# Sensor_ESP32_1_1.net
KiCad netlist of a schematic drawn in EAGLE
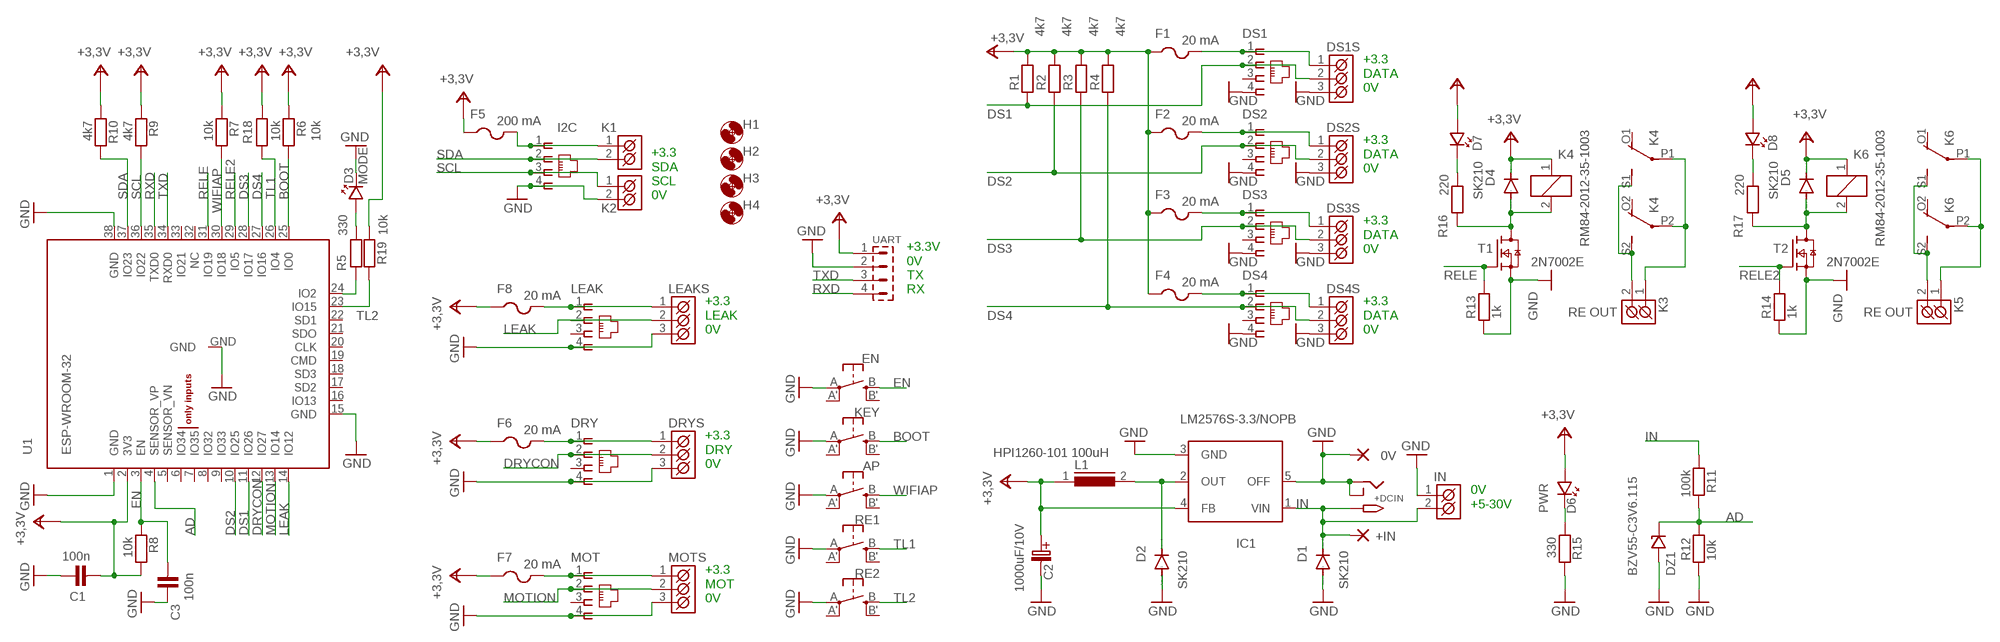
[diagram p0: schematic, sheet 1]

(export (version "E")
  (design (tool "Eeschema 10.0.6"))
  (components
    (comp (ref "+DCIN")
      (value "2.1MMJACKTHM")
      (footprint "eagle-import:PJ-102A")
      (libsource (lib "eagle-import") (part "2.1MMJACKTHM"))
    )
    (comp (ref "+IN")
      (value "SMD2")
      (footprint "eagle-import:SMD1,27-2,54")
      (libsource (lib "eagle-import") (part "SMD2"))
    )
    (comp (ref "0V")
      (value "SMD2")
      (footprint "eagle-import:SMD1,27-2,54")
      (libsource (lib "eagle-import") (part "SMD2"))
    )
    (comp (ref "AP")
      (value "SPST_TACT-EVQQ2")
      (footprint "eagle-import:EVQ-Q2")
      (libsource (lib "eagle-import") (part "SPST_TACT-EVQQ2"))
    )
    (comp (ref "C1")
      (value "100n")
      (footprint "eagle-import:1206")
      (libsource (lib "eagle-import") (part "C-KER_1206"))
    )
    (comp (ref "C2")
      (value "1000uF/10V")
      (footprint "eagle-import:C-EL_5")
      (libsource (lib "eagle-import") (part "C-EL_5"))
    )
    (comp (ref "C3")
      (value "100n")
      (footprint "eagle-import:1206")
      (libsource (lib "eagle-import") (part "C-KER_1206"))
    )
    (comp (ref "D1")
      (value "SK210")
      (footprint "eagle-import:SMB")
      (libsource (lib "eagle-import") (part "DIODE-SMB"))
    )
    (comp (ref "D2")
      (value "SK210")
      (footprint "eagle-import:SMB")
      (libsource (lib "eagle-import") (part "DIODE-SMB"))
    )
    (comp (ref "D3")
      (value "MODE")
      (footprint "eagle-import:P1206")
      (libsource (lib "eagle-import") (part "LED_1206"))
    )
    (comp (ref "D4")
      (value "SK210")
      (footprint "eagle-import:SMB")
      (libsource (lib "eagle-import") (part "DIODE-SMB"))
    )
    (comp (ref "D5")
      (value "SK210")
      (footprint "eagle-import:SMB")
      (libsource (lib "eagle-import") (part "DIODE-SMB"))
    )
    (comp (ref "D6")
      (value "PWR")
      (footprint "eagle-import:P1206")
      (libsource (lib "eagle-import") (part "LED_1206"))
    )
    (comp (ref "D7")
      (value "LED_1206")
      (footprint "eagle-import:P1206")
      (libsource (lib "eagle-import") (part "LED_1206"))
    )
    (comp (ref "D8")
      (value "LED_1206")
      (footprint "eagle-import:P1206")
      (libsource (lib "eagle-import") (part "LED_1206"))
    )
    (comp (ref "DRY")
      (value "WEBP_6_1")
      (footprint "eagle-import:WEBP_6_1")
      (libsource (lib "eagle-import") (part "WEBP_6_1"))
    )
    (comp (ref "DRYS")
      (value "ARK550/3")
      (footprint "eagle-import:ARK550_3")
      (libsource (lib "eagle-import") (part "ARK550/3"))
    )
    (comp (ref "DS1")
      (value "WEBP_6_1")
      (footprint "eagle-import:WEBP_6_1")
      (libsource (lib "eagle-import") (part "WEBP_6_1"))
    )
    (comp (ref "DS1S")
      (value "ARK550/3")
      (footprint "eagle-import:ARK550_3")
      (libsource (lib "eagle-import") (part "ARK550/3"))
    )
    (comp (ref "DS2")
      (value "WEBP_6_1")
      (footprint "eagle-import:WEBP_6_1")
      (libsource (lib "eagle-import") (part "WEBP_6_1"))
    )
    (comp (ref "DS2S")
      (value "ARK550/3")
      (footprint "eagle-import:ARK550_3")
      (libsource (lib "eagle-import") (part "ARK550/3"))
    )
    (comp (ref "DS3")
      (value "WEBP_6_1")
      (footprint "eagle-import:WEBP_6_1")
      (libsource (lib "eagle-import") (part "WEBP_6_1"))
    )
    (comp (ref "DS3S")
      (value "ARK550/3")
      (footprint "eagle-import:ARK550_3")
      (libsource (lib "eagle-import") (part "ARK550/3"))
    )
    (comp (ref "DS4")
      (value "WEBP_6_1")
      (footprint "eagle-import:WEBP_6_1")
      (libsource (lib "eagle-import") (part "WEBP_6_1"))
    )
    (comp (ref "DS4S")
      (value "ARK550/3")
      (footprint "eagle-import:ARK550_3")
      (libsource (lib "eagle-import") (part "ARK550/3"))
    )
    (comp (ref "DZ1")
      (value "BZV55-C3V6.115")
      (footprint "eagle-import:SOD-80")
      (libsource (lib "eagle-import") (part "D-?-ZENERBZV55C_SMD_0,5W"))
    )
    (comp (ref "EN")
      (value "SPST_TACT-EVQQ2")
      (footprint "eagle-import:EVQ-Q2")
      (libsource (lib "eagle-import") (part "SPST_TACT-EVQQ2"))
    )
    (comp (ref "F1")
      (value "20 mA")
      (footprint "eagle-import:R1206")
      (libsource (lib "eagle-import") (part "PTCFUSE-1206"))
    )
    (comp (ref "F2")
      (value "20 mA")
      (footprint "eagle-import:R1206")
      (libsource (lib "eagle-import") (part "PTCFUSE-1206"))
    )
    (comp (ref "F3")
      (value "20 mA")
      (footprint "eagle-import:R1206")
      (libsource (lib "eagle-import") (part "PTCFUSE-1206"))
    )
    (comp (ref "F4")
      (value "20 mA")
      (footprint "eagle-import:R1206")
      (libsource (lib "eagle-import") (part "PTCFUSE-1206"))
    )
    (comp (ref "F5")
      (value "200 mA")
      (footprint "eagle-import:R1206")
      (libsource (lib "eagle-import") (part "PTCFUSE-1206"))
    )
    (comp (ref "F6")
      (value "20 mA")
      (footprint "eagle-import:R1206")
      (libsource (lib "eagle-import") (part "PTCFUSE-1206"))
    )
    (comp (ref "F7")
      (value "20 mA")
      (footprint "eagle-import:R1206")
      (libsource (lib "eagle-import") (part "PTCFUSE-1206"))
    )
    (comp (ref "F8")
      (value "20 mA")
      (footprint "eagle-import:R1206")
      (libsource (lib "eagle-import") (part "PTCFUSE-1206"))
    )
    (comp (ref "H1")
      (value "MOUNT-HOLE3.0")
      (footprint "eagle-import:3,0")
      (libsource (lib "eagle-import") (part "MOUNT-HOLE3.0"))
    )
    (comp (ref "H2")
      (value "MOUNT-HOLE3.0")
      (footprint "eagle-import:3,0")
      (libsource (lib "eagle-import") (part "MOUNT-HOLE3.0"))
    )
    (comp (ref "H3")
      (value "MOUNT-HOLE3.0")
      (footprint "eagle-import:3,0")
      (libsource (lib "eagle-import") (part "MOUNT-HOLE3.0"))
    )
    (comp (ref "H4")
      (value "MOUNT-HOLE3.0")
      (footprint "eagle-import:3,0")
      (libsource (lib "eagle-import") (part "MOUNT-HOLE3.0"))
    )
    (comp (ref "I2C")
      (value "WEBP_6_1")
      (footprint "eagle-import:WEBP_6_1")
      (libsource (lib "eagle-import") (part "WEBP_6_1"))
    )
    (comp (ref "IC1")
      (value "LM2576S-3.3/NOPB")
      (footprint "eagle-import:TO263-5")
      (libsource (lib "eagle-import") (part "LM2576S"))
    )
    (comp (ref "IN")
      (value "ARK550/2")
      (footprint "eagle-import:ARK550_2")
      (libsource (lib "eagle-import") (part "ARK550/2"))
    )
    (comp (ref "K1")
      (value "ARK550/2")
      (footprint "eagle-import:ARK550_2")
      (libsource (lib "eagle-import") (part "ARK550/2"))
    )
    (comp (ref "K2")
      (value "ARK550/2")
      (footprint "eagle-import:ARK550_2")
      (libsource (lib "eagle-import") (part "ARK550/2"))
    )
    (comp (ref "K3")
      (value "RE OUT")
      (footprint "eagle-import:ARK500_2")
      (libsource (lib "eagle-import") (part "ARK500/2"))
    )
    (comp (ref "K4")
      (value "RM84-2012-35-1003")
      (footprint "eagle-import:G2R2")
      (fields (field (name "MF") "OMRON COMPONENTS USA") (field (name "MPN") "G2R-2-DC6"))
      (libsource (lib "eagle-import") (part "G2R2"))
    )
    (comp (ref "K5")
      (value "RE OUT")
      (footprint "eagle-import:ARK500_2")
      (libsource (lib "eagle-import") (part "ARK500/2"))
    )
    (comp (ref "K6")
      (value "RM84-2012-35-1003")
      (footprint "eagle-import:G2R2")
      (fields (field (name "MF") "OMRON COMPONENTS USA") (field (name "MPN") "G2R-2-DC6"))
      (libsource (lib "eagle-import") (part "G2R2"))
    )
    (comp (ref "KEY")
      (value "SPST_TACT-EVQQ2")
      (footprint "eagle-import:EVQ-Q2")
      (libsource (lib "eagle-import") (part "SPST_TACT-EVQQ2"))
    )
    (comp (ref "L1")
      (value "HPI1260-101 100uH")
      (footprint "eagle-import:DR125")
      (libsource (lib "eagle-import") (part "DR125"))
    )
    (comp (ref "LEAK")
      (value "WEBP_6_1")
      (footprint "eagle-import:WEBP_6_1")
      (libsource (lib "eagle-import") (part "WEBP_6_1"))
    )
    (comp (ref "LEAKS")
      (value "ARK550/3")
      (footprint "eagle-import:ARK550_3")
      (libsource (lib "eagle-import") (part "ARK550/3"))
    )
    (comp (ref "MOT")
      (value "WEBP_6_1")
      (footprint "eagle-import:WEBP_6_1")
      (libsource (lib "eagle-import") (part "WEBP_6_1"))
    )
    (comp (ref "MOTS")
      (value "ARK550/3")
      (footprint "eagle-import:ARK550_3")
      (libsource (lib "eagle-import") (part "ARK550/3"))
    )
    (comp (ref "R1")
      (value "4k7")
      (footprint "eagle-import:1206")
      (libsource (lib "eagle-import") (part "R_1206"))
    )
    (comp (ref "R2")
      (value "4k7")
      (footprint "eagle-import:1206")
      (libsource (lib "eagle-import") (part "R_1206"))
    )
    (comp (ref "R3")
      (value "4k7")
      (footprint "eagle-import:1206")
      (libsource (lib "eagle-import") (part "R_1206"))
    )
    (comp (ref "R4")
      (value "4k7")
      (footprint "eagle-import:1206")
      (libsource (lib "eagle-import") (part "R_1206"))
    )
    (comp (ref "R5")
      (value "330")
      (footprint "eagle-import:1206")
      (libsource (lib "eagle-import") (part "R_1206"))
    )
    (comp (ref "R6")
      (value "10k")
      (footprint "eagle-import:1206")
      (libsource (lib "eagle-import") (part "R_1206"))
    )
    (comp (ref "R7")
      (value "10k")
      (footprint "eagle-import:1206")
      (libsource (lib "eagle-import") (part "R_1206"))
    )
    (comp (ref "R8")
      (value "10k")
      (footprint "eagle-import:1206")
      (libsource (lib "eagle-import") (part "R_1206"))
    )
    (comp (ref "R9")
      (value "4k7")
      (footprint "eagle-import:1206")
      (libsource (lib "eagle-import") (part "R_1206"))
    )
    (comp (ref "R10")
      (value "4k7")
      (footprint "eagle-import:1206")
      (libsource (lib "eagle-import") (part "R_1206"))
    )
    (comp (ref "R11")
      (value "100k")
      (footprint "eagle-import:1206")
      (libsource (lib "eagle-import") (part "R_1206"))
    )
    (comp (ref "R12")
      (value "10k")
      (footprint "eagle-import:1206")
      (libsource (lib "eagle-import") (part "R_1206"))
    )
    (comp (ref "R13")
      (value "1k")
      (footprint "eagle-import:1206")
      (libsource (lib "eagle-import") (part "R_1206"))
    )
    (comp (ref "R14")
      (value "1k")
      (footprint "eagle-import:1206")
      (libsource (lib "eagle-import") (part "R_1206"))
    )
    (comp (ref "R15")
      (value "330")
      (footprint "eagle-import:1206")
      (libsource (lib "eagle-import") (part "R_1206"))
    )
    (comp (ref "R16")
      (value "220")
      (footprint "eagle-import:1206")
      (libsource (lib "eagle-import") (part "R_1206"))
    )
    (comp (ref "R17")
      (value "220")
      (footprint "eagle-import:1206")
      (libsource (lib "eagle-import") (part "R_1206"))
    )
    (comp (ref "R18")
      (value "10k")
      (footprint "eagle-import:1206")
      (libsource (lib "eagle-import") (part "R_1206"))
    )
    (comp (ref "R19")
      (value "10k")
      (footprint "eagle-import:1206")
      (libsource (lib "eagle-import") (part "R_1206"))
    )
    (comp (ref "RE1")
      (value "SPST_TACT-EVQQ2")
      (footprint "eagle-import:EVQ-Q2")
      (libsource (lib "eagle-import") (part "SPST_TACT-EVQQ2"))
    )
    (comp (ref "RE2")
      (value "SPST_TACT-EVQQ2")
      (footprint "eagle-import:EVQ-Q2")
      (libsource (lib "eagle-import") (part "SPST_TACT-EVQQ2"))
    )
    (comp (ref "T1")
      (value "2N7002E")
      (footprint "eagle-import:SOT23")
      (libsource (lib "eagle-import") (part "2N7002E"))
    )
    (comp (ref "T2")
      (value "2N7002E")
      (footprint "eagle-import:SOT23")
      (libsource (lib "eagle-import") (part "2N7002E"))
    )
    (comp (ref "U1")
      (value "ESP-WROOM-32")
      (footprint "eagle-import:ESP-WROOM-32")
      (libsource (lib "eagle-import") (part "ESP-WROOM-32"))
    )
    (comp (ref "UART")
      (value "S1G4_JUMP")
      (footprint "eagle-import:S1G4_JUM")
      (libsource (lib "eagle-import") (part "S1G4_JUMP"))
    )
  )
  (nets
    (net (code "1") (name "+3,3V") (class "Default")
      (node (ref "C1") (pin "2") (pinfunction "2_2") (pintype "passive"))
      (node (ref "C2") (pin "C+") (pinfunction "C_EL+_C+") (pintype "passive"))
      (node (ref "D4") (pin "C") (pinfunction "C_C") (pintype "passive"))
      (node (ref "D5") (pin "C") (pinfunction "C_C") (pintype "passive"))
      (node (ref "D6") (pin "A") (pinfunction "A_A") (pintype "passive"))
      (node (ref "D7") (pin "A") (pinfunction "A_A") (pintype "passive"))
      (node (ref "D8") (pin "A") (pinfunction "A_A") (pintype "passive"))
      (node (ref "F1") (pin "1") (pinfunction "1_1") (pintype "passive"))
      (node (ref "F2") (pin "1") (pinfunction "1_1") (pintype "passive"))
      (node (ref "F3") (pin "1") (pinfunction "1_1") (pintype "passive"))
      (node (ref "F4") (pin "1") (pinfunction "1_1") (pintype "passive"))
      (node (ref "F5") (pin "1") (pinfunction "1_1") (pintype "passive"))
      (node (ref "F6") (pin "1") (pinfunction "1_1") (pintype "passive"))
      (node (ref "F7") (pin "1") (pinfunction "1_1") (pintype "passive"))
      (node (ref "F8") (pin "1") (pinfunction "1_1") (pintype "passive"))
      (node (ref "IC1") (pin "4") (pinfunction "FB_4") (pintype "input"))
      (node (ref "K4") (pin "1") (pinfunction "1_1") (pintype "passive"))
      (node (ref "K6") (pin "1") (pinfunction "1_1") (pintype "passive"))
      (node (ref "L1") (pin "1") (pinfunction "1_1") (pintype "passive"))
      (node (ref "R1") (pin "2") (pinfunction "2_2") (pintype "passive"))
      (node (ref "R10") (pin "1") (pinfunction "1_1") (pintype "passive"))
      (node (ref "R18") (pin "1") (pinfunction "1_1") (pintype "passive"))
      (node (ref "R19") (pin "1") (pinfunction "1_1") (pintype "passive"))
      (node (ref "R2") (pin "2") (pinfunction "2_2") (pintype "passive"))
      (node (ref "R3") (pin "2") (pinfunction "2_2") (pintype "passive"))
      (node (ref "R4") (pin "2") (pinfunction "2_2") (pintype "passive"))
      (node (ref "R6") (pin "1") (pinfunction "1_1") (pintype "passive"))
      (node (ref "R7") (pin "1") (pinfunction "1_1") (pintype "passive"))
      (node (ref "R8") (pin "2") (pinfunction "2_2") (pintype "passive"))
      (node (ref "R9") (pin "1") (pinfunction "1_1") (pintype "passive"))
      (node (ref "U1") (pin "2") (pinfunction "3V3_2") (pintype "bidirectional"))
      (node (ref "UART") (pin "1") (pinfunction "1_1") (pintype "passive"))
    )
    (net (code "2") (name "/AD") (class "Default")
      (node (ref "DZ1") (pin "K") (pinfunction "K_K") (pintype "passive"))
      (node (ref "R11") (pin "2") (pinfunction "2_2") (pintype "passive"))
      (node (ref "R12") (pin "2") (pinfunction "2_2") (pintype "passive"))
      (node (ref "U1") (pin "4") (pinfunction "SENSOR_VP_4") (pintype "input"))
    )
    (net (code "3") (name "/BOOT") (class "Default")
      (node (ref "KEY") (pin "B") (pinfunction "S_B") (pintype "passive"))
      (node (ref "R6") (pin "2") (pinfunction "2_2") (pintype "passive"))
      (node (ref "U1") (pin "25") (pinfunction "IO0_25") (pintype "bidirectional"))
    )
    (net (code "4") (name "/DRYCON") (class "Default")
      (node (ref "DRY") (pin "2") (pinfunction "2_2") (pintype "passive"))
      (node (ref "DRYS") (pin "2") (pinfunction "K2_2") (pintype "passive"))
      (node (ref "U1") (pin "12") (pinfunction "IO27_12") (pintype "bidirectional"))
    )
    (net (code "5") (name "/DS1") (class "Default")
      (node (ref "DS1") (pin "2") (pinfunction "2_2") (pintype "passive"))
      (node (ref "DS1S") (pin "2") (pinfunction "K2_2") (pintype "passive"))
      (node (ref "R1") (pin "1") (pinfunction "1_1") (pintype "passive"))
      (node (ref "U1") (pin "11") (pinfunction "IO26_11") (pintype "bidirectional"))
    )
    (net (code "6") (name "/DS2") (class "Default")
      (node (ref "DS2") (pin "2") (pinfunction "2_2") (pintype "passive"))
      (node (ref "DS2S") (pin "2") (pinfunction "K2_2") (pintype "passive"))
      (node (ref "R2") (pin "1") (pinfunction "1_1") (pintype "passive"))
      (node (ref "U1") (pin "10") (pinfunction "IO25_10") (pintype "bidirectional"))
    )
    (net (code "7") (name "/DS3") (class "Default")
      (node (ref "DS3") (pin "2") (pinfunction "2_2") (pintype "passive"))
      (node (ref "DS3S") (pin "2") (pinfunction "K2_2") (pintype "passive"))
      (node (ref "R3") (pin "1") (pinfunction "1_1") (pintype "passive"))
      (node (ref "U1") (pin "28") (pinfunction "IO17_28") (pintype "bidirectional"))
    )
    (net (code "8") (name "/DS4") (class "Default")
      (node (ref "DS4") (pin "2") (pinfunction "2_2") (pintype "passive"))
      (node (ref "DS4S") (pin "2") (pinfunction "K2_2") (pintype "passive"))
      (node (ref "R4") (pin "1") (pinfunction "1_1") (pintype "passive"))
      (node (ref "U1") (pin "27") (pinfunction "IO16_27") (pintype "bidirectional"))
    )
    (net (code "9") (name "/EN") (class "Default")
      (node (ref "C3") (pin "2") (pinfunction "2_2") (pintype "passive"))
      (node (ref "EN") (pin "B") (pinfunction "S_B") (pintype "passive"))
      (node (ref "R8") (pin "1") (pinfunction "1_1") (pintype "passive"))
      (node (ref "U1") (pin "3") (pinfunction "EN_3") (pintype "bidirectional"))
    )
    (net (code "10") (name "/IN") (class "Default")
      (node (ref "+DCIN") (pin "TIP") (pinfunction "TIP_TIP") (pintype "bidirectional"))
      (node (ref "+IN") (pin "1") (pinfunction "P_1") (pintype "passive"))
      (node (ref "D1") (pin "C") (pinfunction "C_C") (pintype "passive"))
      (node (ref "IC1") (pin "1") (pinfunction "VIN_1") (pintype "power_in"))
      (node (ref "IN") (pin "2") (pinfunction "K2_2") (pintype "passive"))
      (node (ref "R11") (pin "1") (pinfunction "1_1") (pintype "passive"))
    )
    (net (code "11") (name "/LEAK") (class "Default")
      (node (ref "LEAK") (pin "2") (pinfunction "2_2") (pintype "passive"))
      (node (ref "LEAKS") (pin "2") (pinfunction "K2_2") (pintype "passive"))
      (node (ref "U1") (pin "14") (pinfunction "IO12_14") (pintype "bidirectional"))
    )
    (net (code "12") (name "/MOTION") (class "Default")
      (node (ref "MOT") (pin "2") (pinfunction "2_2") (pintype "passive"))
      (node (ref "MOTS") (pin "2") (pinfunction "K2_2") (pintype "passive"))
      (node (ref "U1") (pin "13") (pinfunction "IO14_13") (pintype "bidirectional"))
    )
    (net (code "13") (name "/RELE") (class "Default")
      (node (ref "R13") (pin "2") (pinfunction "2_2") (pintype "passive"))
      (node (ref "T1") (pin "1") (pinfunction "G_1") (pintype "passive"))
      (node (ref "U1") (pin "31") (pinfunction "IO19_31") (pintype "bidirectional"))
    )
    (net (code "14") (name "/RELE2") (class "Default")
      (node (ref "R14") (pin "2") (pinfunction "2_2") (pintype "passive"))
      (node (ref "T2") (pin "1") (pinfunction "G_1") (pintype "passive"))
      (node (ref "U1") (pin "29") (pinfunction "IO5_29") (pintype "bidirectional"))
    )
    (net (code "15") (name "/RXD") (class "Default")
      (node (ref "U1") (pin "35") (pinfunction "TXD0_35") (pintype "bidirectional"))
      (node (ref "UART") (pin "4") (pinfunction "4_4") (pintype "passive"))
    )
    (net (code "16") (name "/SCL") (class "Default")
      (node (ref "I2C") (pin "3") (pinfunction "3_3") (pintype "passive"))
      (node (ref "K2") (pin "1") (pinfunction "K1_1") (pintype "passive"))
      (node (ref "R9") (pin "2") (pinfunction "2_2") (pintype "passive"))
      (node (ref "U1") (pin "36") (pinfunction "IO22_36") (pintype "bidirectional"))
    )
    (net (code "17") (name "/SDA") (class "Default")
      (node (ref "I2C") (pin "2") (pinfunction "2_2") (pintype "passive"))
      (node (ref "K1") (pin "2") (pinfunction "K2_2") (pintype "passive"))
      (node (ref "R10") (pin "2") (pinfunction "2_2") (pintype "passive"))
      (node (ref "U1") (pin "37") (pinfunction "IO23_37") (pintype "bidirectional"))
    )
    (net (code "18") (name "/TL1") (class "Default")
      (node (ref "R18") (pin "2") (pinfunction "2_2") (pintype "passive"))
      (node (ref "RE1") (pin "B") (pinfunction "S_B") (pintype "passive"))
      (node (ref "U1") (pin "26") (pinfunction "IO4_26") (pintype "bidirectional"))
    )
    (net (code "19") (name "/TL2") (class "Default")
      (node (ref "R19") (pin "2") (pinfunction "2_2") (pintype "passive"))
      (node (ref "RE2") (pin "B") (pinfunction "S_B") (pintype "passive"))
      (node (ref "U1") (pin "23") (pinfunction "IO15_23") (pintype "bidirectional"))
    )
    (net (code "20") (name "/TXD") (class "Default")
      (node (ref "U1") (pin "34") (pinfunction "RXD0_34") (pintype "bidirectional"))
      (node (ref "UART") (pin "3") (pinfunction "3_3") (pintype "passive"))
    )
    (net (code "21") (name "/WIFIAP") (class "Default")
      (node (ref "AP") (pin "B") (pinfunction "S_B") (pintype "passive"))
      (node (ref "R7") (pin "2") (pinfunction "2_2") (pintype "passive"))
      (node (ref "U1") (pin "30") (pinfunction "IO18_30") (pintype "bidirectional"))
    )
    (net (code "22") (name "GND") (class "Default")
      (node (ref "+DCIN") (pin "RING") (pinfunction "RING_RING") (pintype "bidirectional"))
      (node (ref "+DCIN") (pin "RING_SW") (pinfunction "RING_SW_RING_SW") (pintype "bidirectional"))
      (node (ref "0V") (pin "1") (pinfunction "P_1") (pintype "passive"))
      (node (ref "AP") (pin "A") (pinfunction "P_A") (pintype "passive"))
      (node (ref "C1") (pin "1") (pinfunction "1_1") (pintype "passive"))
      (node (ref "C2") (pin "C-") (pinfunction "C_EL-_C-") (pintype "passive"))
      (node (ref "C3") (pin "1") (pinfunction "1_1") (pintype "passive"))
      (node (ref "D1") (pin "A") (pinfunction "A_A") (pintype "passive"))
      (node (ref "D2") (pin "A") (pinfunction "A_A") (pintype "passive"))
      (node (ref "D3") (pin "K") (pinfunction "K_K") (pintype "passive"))
      (node (ref "DRY") (pin "4") (pinfunction "4_4") (pintype "passive"))
      (node (ref "DRYS") (pin "3") (pinfunction "K3_3") (pintype "passive"))
      (node (ref "DS1") (pin "4") (pinfunction "4_4") (pintype "passive"))
      (node (ref "DS1S") (pin "3") (pinfunction "K3_3") (pintype "passive"))
      (node (ref "DS2") (pin "4") (pinfunction "4_4") (pintype "passive"))
      (node (ref "DS2S") (pin "3") (pinfunction "K3_3") (pintype "passive"))
      (node (ref "DS3") (pin "4") (pinfunction "4_4") (pintype "passive"))
      (node (ref "DS3S") (pin "3") (pinfunction "K3_3") (pintype "passive"))
      (node (ref "DS4") (pin "4") (pinfunction "4_4") (pintype "passive"))
      (node (ref "DS4S") (pin "3") (pinfunction "K3_3") (pintype "passive"))
      (node (ref "DZ1") (pin "A") (pinfunction "A_A") (pintype "passive"))
      (node (ref "EN") (pin "A") (pinfunction "P_A") (pintype "passive"))
      (node (ref "I2C") (pin "4") (pinfunction "4_4") (pintype "passive"))
      (node (ref "IC1") (pin "3") (pinfunction "GND_3") (pintype "power_in"))
      (node (ref "IC1") (pin "5") (pinfunction "OFF_5") (pintype "input"))
      (node (ref "IN") (pin "1") (pinfunction "K1_1") (pintype "passive"))
      (node (ref "K2") (pin "2") (pinfunction "K2_2") (pintype "passive"))
      (node (ref "KEY") (pin "A") (pinfunction "P_A") (pintype "passive"))
      (node (ref "LEAK") (pin "4") (pinfunction "4_4") (pintype "passive"))
      (node (ref "LEAKS") (pin "3") (pinfunction "K3_3") (pintype "passive"))
      (node (ref "MOT") (pin "4") (pinfunction "4_4") (pintype "passive"))
      (node (ref "MOTS") (pin "3") (pinfunction "K3_3") (pintype "passive"))
      (node (ref "R12") (pin "1") (pinfunction "1_1") (pintype "passive"))
      (node (ref "R13") (pin "1") (pinfunction "1_1") (pintype "passive"))
      (node (ref "R14") (pin "1") (pinfunction "1_1") (pintype "passive"))
      (node (ref "R15") (pin "2") (pinfunction "2_2") (pintype "passive"))
      (node (ref "RE1") (pin "A") (pinfunction "P_A") (pintype "passive"))
      (node (ref "RE2") (pin "A") (pinfunction "P_A") (pintype "passive"))
      (node (ref "T1") (pin "2") (pinfunction "S_2") (pintype "passive"))
      (node (ref "T2") (pin "2") (pinfunction "S_2") (pintype "passive"))
      (node (ref "U1") (pin "1") (pinfunction "GND_1") (pintype "bidirectional"))
      (node (ref "U1") (pin "15") (pinfunction "GND_15") (pintype "bidirectional"))
      (node (ref "U1") (pin "38") (pinfunction "GND_38") (pintype "bidirectional"))
      (node (ref "U1") (pin "GND") (pinfunction "GND_GND") (pintype "bidirectional"))
      (node (ref "UART") (pin "2") (pinfunction "2_2") (pintype "passive"))
    )
    (net (code "23") (name "Net-(D3-PadA)") (class "Default")
      (node (ref "D3") (pin "A") (pinfunction "A_A") (pintype "passive"))
      (node (ref "R5") (pin "1") (pinfunction "1_1") (pintype "passive"))
    )
    (net (code "24") (name "Net-(D6-PadK)") (class "Default")
      (node (ref "D6") (pin "K") (pinfunction "K_K") (pintype "passive"))
      (node (ref "R15") (pin "1") (pinfunction "1_1") (pintype "passive"))
    )
    (net (code "25") (name "Net-(D7-PadK)") (class "Default")
      (node (ref "D7") (pin "K") (pinfunction "K_K") (pintype "passive"))
      (node (ref "R16") (pin "1") (pinfunction "1_1") (pintype "passive"))
    )
    (net (code "26") (name "Net-(D8-PadK)") (class "Default")
      (node (ref "D8") (pin "K") (pinfunction "K_K") (pintype "passive"))
      (node (ref "R17") (pin "1") (pinfunction "1_1") (pintype "passive"))
    )
    (net (code "27") (name "Net-(DRYS-K1)") (class "Default")
      (node (ref "DRY") (pin "1") (pinfunction "1_1") (pintype "passive"))
      (node (ref "DRYS") (pin "1") (pinfunction "K1_1") (pintype "passive"))
      (node (ref "F6") (pin "2") (pinfunction "2_2") (pintype "passive"))
    )
    (net (code "28") (name "Net-(DS1S-K1)") (class "Default")
      (node (ref "DS1") (pin "1") (pinfunction "1_1") (pintype "passive"))
      (node (ref "DS1S") (pin "1") (pinfunction "K1_1") (pintype "passive"))
      (node (ref "F1") (pin "2") (pinfunction "2_2") (pintype "passive"))
    )
    (net (code "29") (name "Net-(DS2S-K1)") (class "Default")
      (node (ref "DS2") (pin "1") (pinfunction "1_1") (pintype "passive"))
      (node (ref "DS2S") (pin "1") (pinfunction "K1_1") (pintype "passive"))
      (node (ref "F2") (pin "2") (pinfunction "2_2") (pintype "passive"))
    )
    (net (code "30") (name "Net-(DS3S-K1)") (class "Default")
      (node (ref "DS3") (pin "1") (pinfunction "1_1") (pintype "passive"))
      (node (ref "DS3S") (pin "1") (pinfunction "K1_1") (pintype "passive"))
      (node (ref "F3") (pin "2") (pinfunction "2_2") (pintype "passive"))
    )
    (net (code "31") (name "Net-(DS4S-K1)") (class "Default")
      (node (ref "DS4") (pin "1") (pinfunction "1_1") (pintype "passive"))
      (node (ref "DS4S") (pin "1") (pinfunction "K1_1") (pintype "passive"))
      (node (ref "F4") (pin "2") (pinfunction "2_2") (pintype "passive"))
    )
    (net (code "32") (name "Net-(IC1-OUT)") (class "Default")
      (node (ref "D2") (pin "C") (pinfunction "C_C") (pintype "passive"))
      (node (ref "IC1") (pin "2") (pinfunction "OUT_2") (pintype "output"))
      (node (ref "L1") (pin "2") (pinfunction "2_2") (pintype "passive"))
    )
    (net (code "33") (name "Net-(K1-K1)") (class "Default")
      (node (ref "F5") (pin "2") (pinfunction "2_2") (pintype "passive"))
      (node (ref "I2C") (pin "1") (pinfunction "1_1") (pintype "passive"))
      (node (ref "K1") (pin "1") (pinfunction "K1_1") (pintype "passive"))
    )
    (net (code "34") (name "Net-(K3-K1)") (class "Default")
      (node (ref "K3") (pin "1") (pinfunction "K1_1") (pintype "passive"))
      (node (ref "K4") (pin "P1") (pinfunction "P_P1") (pintype "passive"))
      (node (ref "K4") (pin "P2") (pinfunction "P_P2") (pintype "passive"))
    )
    (net (code "35") (name "Net-(K3-K2)") (class "Default")
      (node (ref "K3") (pin "2") (pinfunction "K2_2") (pintype "passive"))
      (node (ref "K4") (pin "S1") (pinfunction "S_S1") (pintype "passive"))
      (node (ref "K4") (pin "S2") (pinfunction "S_S2") (pintype "passive"))
    )
    (net (code "36") (name "Net-(K5-K1)") (class "Default")
      (node (ref "K5") (pin "1") (pinfunction "K1_1") (pintype "passive"))
      (node (ref "K6") (pin "P1") (pinfunction "P_P1") (pintype "passive"))
      (node (ref "K6") (pin "P2") (pinfunction "P_P2") (pintype "passive"))
    )
    (net (code "37") (name "Net-(K5-K2)") (class "Default")
      (node (ref "K5") (pin "2") (pinfunction "K2_2") (pintype "passive"))
      (node (ref "K6") (pin "S1") (pinfunction "S_S1") (pintype "passive"))
      (node (ref "K6") (pin "S2") (pinfunction "S_S2") (pintype "passive"))
    )
    (net (code "38") (name "Net-(LEAKS-K1)") (class "Default")
      (node (ref "F8") (pin "2") (pinfunction "2_2") (pintype "passive"))
      (node (ref "LEAK") (pin "1") (pinfunction "1_1") (pintype "passive"))
      (node (ref "LEAKS") (pin "1") (pinfunction "K1_1") (pintype "passive"))
    )
    (net (code "39") (name "Net-(MOTS-K1)") (class "Default")
      (node (ref "F7") (pin "2") (pinfunction "2_2") (pintype "passive"))
      (node (ref "MOT") (pin "1") (pinfunction "1_1") (pintype "passive"))
      (node (ref "MOTS") (pin "1") (pinfunction "K1_1") (pintype "passive"))
    )
    (net (code "40") (name "Net-(T1-D)") (class "Default")
      (node (ref "D4") (pin "A") (pinfunction "A_A") (pintype "passive"))
      (node (ref "K4") (pin "2") (pinfunction "2_2") (pintype "passive"))
      (node (ref "R16") (pin "2") (pinfunction "2_2") (pintype "passive"))
      (node (ref "T1") (pin "3") (pinfunction "D_3") (pintype "passive"))
    )
    (net (code "41") (name "Net-(T2-D)") (class "Default")
      (node (ref "D5") (pin "A") (pinfunction "A_A") (pintype "passive"))
      (node (ref "K6") (pin "2") (pinfunction "2_2") (pintype "passive"))
      (node (ref "R17") (pin "2") (pinfunction "2_2") (pintype "passive"))
      (node (ref "T2") (pin "3") (pinfunction "D_3") (pintype "passive"))
    )
    (net (code "42") (name "Net-(U1-IO2)") (class "Default")
      (node (ref "R5") (pin "2") (pinfunction "2_2") (pintype "passive"))
      (node (ref "U1") (pin "24") (pinfunction "IO2_24") (pintype "bidirectional"))
    )
    (net (code "43") (name "unconnected-(AP-P1-PadA')") (class "Default")
      (node (ref "AP") (pin "A'") (pinfunction "P1_A'") (pintype "passive"))
    )
    (net (code "44") (name "unconnected-(AP-S1-PadB')") (class "Default")
      (node (ref "AP") (pin "B'") (pinfunction "S1_B'") (pintype "passive"))
    )
    (net (code "45") (name "unconnected-(DRY-Pad3)") (class "Default")
      (node (ref "DRY") (pin "3") (pinfunction "3_3") (pintype "passive"))
    )
    (net (code "46") (name "unconnected-(DS1-Pad3)") (class "Default")
      (node (ref "DS1") (pin "3") (pinfunction "3_3") (pintype "passive"))
    )
    (net (code "47") (name "unconnected-(DS2-Pad3)") (class "Default")
      (node (ref "DS2") (pin "3") (pinfunction "3_3") (pintype "passive"))
    )
    (net (code "48") (name "unconnected-(DS3-Pad3)") (class "Default")
      (node (ref "DS3") (pin "3") (pinfunction "3_3") (pintype "passive"))
    )
    (net (code "49") (name "unconnected-(DS4-Pad3)") (class "Default")
      (node (ref "DS4") (pin "3") (pinfunction "3_3") (pintype "passive"))
    )
    (net (code "50") (name "unconnected-(EN-P1-PadA')") (class "Default")
      (node (ref "EN") (pin "A'") (pinfunction "P1_A'") (pintype "passive"))
    )
    (net (code "51") (name "unconnected-(EN-S1-PadB')") (class "Default")
      (node (ref "EN") (pin "B'") (pinfunction "S1_B'") (pintype "passive"))
    )
    (net (code "52") (name "unconnected-(K4B-O-PadO1)") (class "Default")
      (node (ref "K4") (pin "O1") (pinfunction "O_O1") (pintype "passive"))
    )
    (net (code "53") (name "unconnected-(K4C-O-PadO2)") (class "Default")
      (node (ref "K4") (pin "O2") (pinfunction "O_O2") (pintype "passive"))
    )
    (net (code "54") (name "unconnected-(K6B-O-PadO1)") (class "Default")
      (node (ref "K6") (pin "O1") (pinfunction "O_O1") (pintype "passive"))
    )
    (net (code "55") (name "unconnected-(K6C-O-PadO2)") (class "Default")
      (node (ref "K6") (pin "O2") (pinfunction "O_O2") (pintype "passive"))
    )
    (net (code "56") (name "unconnected-(KEY-P1-PadA')") (class "Default")
      (node (ref "KEY") (pin "A'") (pinfunction "P1_A'") (pintype "passive"))
    )
    (net (code "57") (name "unconnected-(KEY-S1-PadB')") (class "Default")
      (node (ref "KEY") (pin "B'") (pinfunction "S1_B'") (pintype "passive"))
    )
    (net (code "58") (name "unconnected-(LEAK-Pad3)") (class "Default")
      (node (ref "LEAK") (pin "3") (pinfunction "3_3") (pintype "passive"))
    )
    (net (code "59") (name "unconnected-(MOT-Pad3)") (class "Default")
      (node (ref "MOT") (pin "3") (pinfunction "3_3") (pintype "passive"))
    )
    (net (code "60") (name "unconnected-(RE1-P1-PadA')") (class "Default")
      (node (ref "RE1") (pin "A'") (pinfunction "P1_A'") (pintype "passive"))
    )
    (net (code "61") (name "unconnected-(RE1-S1-PadB')") (class "Default")
      (node (ref "RE1") (pin "B'") (pinfunction "S1_B'") (pintype "passive"))
    )
    (net (code "62") (name "unconnected-(RE2-P1-PadA')") (class "Default")
      (node (ref "RE2") (pin "A'") (pinfunction "P1_A'") (pintype "passive"))
    )
    (net (code "63") (name "unconnected-(RE2-S1-PadB')") (class "Default")
      (node (ref "RE2") (pin "B'") (pinfunction "S1_B'") (pintype "passive"))
    )
    (net (code "64") (name "unconnected-(U1-CLK-Pad20)") (class "Default")
      (node (ref "U1") (pin "20") (pinfunction "CLK_20") (pintype "bidirectional"))
    )
    (net (code "65") (name "unconnected-(U1-CMD-Pad19)") (class "Default")
      (node (ref "U1") (pin "19") (pinfunction "CMD_19") (pintype "bidirectional"))
    )
    (net (code "66") (name "unconnected-(U1-IO13-Pad16)") (class "Default")
      (node (ref "U1") (pin "16") (pinfunction "IO13_16") (pintype "bidirectional"))
    )
    (net (code "67") (name "unconnected-(U1-IO21-Pad33)") (class "Default")
      (node (ref "U1") (pin "33") (pinfunction "IO21_33") (pintype "bidirectional"))
    )
    (net (code "68") (name "unconnected-(U1-IO32-Pad8)") (class "Default")
      (node (ref "U1") (pin "8") (pinfunction "IO32_8") (pintype "bidirectional"))
    )
    (net (code "69") (name "unconnected-(U1-IO33-Pad9)") (class "Default")
      (node (ref "U1") (pin "9") (pinfunction "IO33_9") (pintype "bidirectional"))
    )
    (net (code "70") (name "unconnected-(U1-IO34-Pad6)") (class "Default")
      (node (ref "U1") (pin "6") (pinfunction "IO34_6") (pintype "input"))
    )
    (net (code "71") (name "unconnected-(U1-IO35-Pad7)") (class "Default")
      (node (ref "U1") (pin "7") (pinfunction "IO35_7") (pintype "input"))
    )
    (net (code "72") (name "unconnected-(U1-NC-Pad32)") (class "Default")
      (node (ref "U1") (pin "32") (pinfunction "NC_32") (pintype "bidirectional"))
    )
    (net (code "73") (name "unconnected-(U1-SD1-Pad22)") (class "Default")
      (node (ref "U1") (pin "22") (pinfunction "SD1_22") (pintype "bidirectional"))
    )
    (net (code "74") (name "unconnected-(U1-SD2-Pad17)") (class "Default")
      (node (ref "U1") (pin "17") (pinfunction "SD2_17") (pintype "bidirectional"))
    )
    (net (code "75") (name "unconnected-(U1-SD3-Pad18)") (class "Default")
      (node (ref "U1") (pin "18") (pinfunction "SD3_18") (pintype "bidirectional"))
    )
    (net (code "76") (name "unconnected-(U1-SDO-Pad21)") (class "Default")
      (node (ref "U1") (pin "21") (pinfunction "SDO_21") (pintype "bidirectional"))
    )
    (net (code "77") (name "unconnected-(U1-SENSOR_VN-Pad5)") (class "Default")
      (node (ref "U1") (pin "5") (pinfunction "SENSOR_VN_5") (pintype "input"))
    )
  )
)
